# Sheet2.net
KiCad netlist of a schematic drawn in Altium Designer
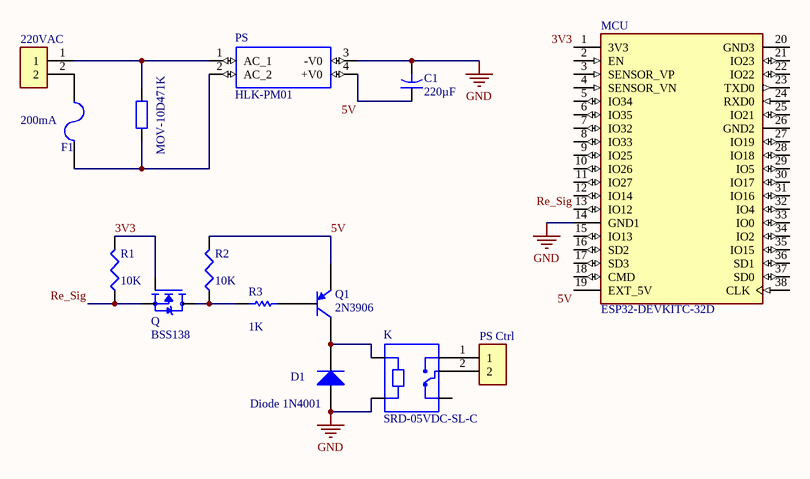
[diagram p0: Sheet2.SchDoc]

(export (version "E")
  (design (tool "Eeschema 10.0.6"))
  (components
    (comp (ref "220VAC")
      (value "282837-2")
      (footprint "TE_282837-2")
      (description "Connector Terminal Blocks Receptacle 2 Position 5.08mm Solder Straight Thru-Hole 13.5A/Contact")
      (fields (field (name "MF") "TE Connectivity") (field (name "DIGI-KEY_PART_NUMBER") "A113320-ND"))
      (libsource (lib "") (part "282837-2_1"))
    )
    (comp (ref "C1")
      (value "220µF")
      (footprint "CAPR5-4X5")
      (description "Capacitor")
      (fields (field (name "Comment") "Cap2") (field (name "PUBLISHER") "Altium Limited"))
      (libsource (lib "Miscellaneous Devices") (part "Cap2"))
    )
    (comp (ref "D1")
      (value "Diode 1N4001")
      (footprint "DO-41")
      (description "1 Amp General Purpose Rectifier")
      (fields (field (name "PUBLISHER") "Altium Limited"))
      (libsource (lib "Miscellaneous Devices") (part "Diode 1N4001"))
    )
    (comp (ref "F1")
      (value "200mA")
      (footprint "PIN-W2/E2.8")
      (description "Fuse")
      (fields (field (name "PUBLISHER") "Altium Limited"))
      (libsource (lib "Miscellaneous Devices") (part "Fuse 2"))
    )
    (comp (ref "K")
      (value "SRD-05VDC-SL-C")
      (footprint "RELAY_SRD-05VDC-SL-C")
      (description "5V Trigger Relay")
      (fields (field (name "MF") "Songle Relay"))
      (libsource (lib "SRD-05VDC-SL-C") (part "SRD-05VDC-SL-C"))
    )
    (comp (ref "MCU")
      (value "ESP32-DEVKITC-32D")
      (footprint "MODULE_ESP32-DEVKITC-32D")
      (fields (field (name "MF") "Espressif Systems"))
      (libsource (lib "ESP32-DEVKITC-32D") (part "ESP32-DEVKITC-32D"))
    )
    (comp (ref "PS")
      (value "HLK-PM01")
      (footprint "HLKPM01")
      (fields (field (name "MF") "Hi-link") (field (name "MP") "hlk-pm01"))
      (libsource (lib "HLK-PM01") (part "HLK-PM01"))
    )
    (comp (ref "PS Ctrl")
      (value "282837-2")
      (footprint "TE_282837-2")
      (description "Connector Terminal Blocks Receptacle 2 Position 5.08mm Solder Straight Thru-Hole 13.5A/Contact")
      (fields (field (name "MF") "TE Connectivity") (field (name "DIGI-KEY_PART_NUMBER") "A113320-ND"))
      (libsource (lib "282837-2") (part "282837-2"))
    )
    (comp (ref "Q")
      (value "BSS138")
      (footprint "SOT95P240X111-3N")
      (description "N-Channel 50V 220mA (Ta) 360mW (Ta) Surface Mount SOT-23-3")
      (fields (field (name "MF") "MICROSS/On Semiconductor"))
      (libsource (lib "BSS138") (part "BSS138"))
    )
    (comp (ref "Q1")
      (value "2N3906")
      (footprint "TO-92A")
      (description "PNP General Purpose Amplifier")
      (fields (field (name "PUBLISHER") "Altium Limited"))
      (libsource (lib "Miscellaneous Devices") (part "2N3906"))
    )
    (comp (ref "R1")
      (value "10K")
      (footprint "J1-0603")
      (description "Resistor")
      (fields (field (name "Comment") "Res3") (field (name "PUBLISHER") "Altium Limited"))
      (libsource (lib "Miscellaneous Devices") (part "Res3"))
    )
    (comp (ref "R2")
      (value "10K")
      (footprint "J1-0603")
      (description "Resistor")
      (fields (field (name "Comment") "Res3") (field (name "PUBLISHER") "Altium Limited"))
      (libsource (lib "Miscellaneous Devices") (part "Res3"))
    )
    (comp (ref "R3")
      (value "1K")
      (footprint "AXIAL-0.3")
      (description "Resistor")
      (fields (field (name "PUBLISHER") "Altium Limited"))
      (libsource (lib "Miscellaneous Devices") (part "Res1"))
    )
    (comp (ref "VAR1")
      (value "MOV-10D471K")
      (footprint "AXIAL-0.4")
      (fields (field (name "PUBLISHER") "Altium Limited"))
      (libsource (lib "Miscellaneous Devices") (part "Res2"))
    )
  )
  (nets
    (net (code "1") (name "/3V3") (class "Default")
      (node (ref "MCU") (pin "1") (pinfunction "3V3_1") (pintype "power_in"))
      (node (ref "Q") (pin "1") (pinfunction "G_1") (pintype "passive"))
      (node (ref "R1") (pin "2") (pinfunction "2_2") (pintype "passive"))
    )
    (net (code "2") (name "/5V") (class "Default")
      (node (ref "C1") (pin "1") (pinfunction "1_1") (pintype "passive"))
      (node (ref "MCU") (pin "19") (pinfunction "EXT_5V_19") (pintype "power_in"))
      (node (ref "PS") (pin "4") (pinfunction "+V0_4") (pintype "bidirectional"))
      (node (ref "Q1") (pin "1") (pinfunction "E_1") (pintype "passive"))
      (node (ref "R2") (pin "2") (pinfunction "2_2") (pintype "passive"))
    )
    (net (code "3") (name "/Re_Sig") (class "Default")
      (node (ref "MCU") (pin "13") (pinfunction "IO12_13") (pintype "bidirectional"))
      (node (ref "Q") (pin "2") (pinfunction "S_2") (pintype "passive"))
      (node (ref "R1") (pin "1") (pinfunction "1_1") (pintype "passive"))
    )
    (net (code "4") (name "GND") (class "Default")
      (node (ref "C1") (pin "2") (pinfunction "2_2") (pintype "passive"))
      (node (ref "D1") (pin "1") (pinfunction "A_1") (pintype "passive"))
      (node (ref "K") (pin "A2") (pinfunction "A2_A2") (pintype "passive"))
      (node (ref "MCU") (pin "14") (pinfunction "GND1_14") (pintype "power_in"))
      (node (ref "PS") (pin "3") (pinfunction "-V0_3") (pintype "bidirectional"))
    )
    (net (code "5") (name "Net-(220VAC-Pad2)") (class "Default")
      (node (ref "220VAC") (pin "2") (pinfunction "2_2") (pintype "passive"))
      (node (ref "F1") (pin "2") (pinfunction "2_2") (pintype "passive"))
    )
    (net (code "6") (name "Net-(D1-K)") (class "Default")
      (node (ref "D1") (pin "2") (pinfunction "K_2") (pintype "passive"))
      (node (ref "K") (pin "A1") (pinfunction "A1_A1") (pintype "passive"))
      (node (ref "Q1") (pin "3") (pinfunction "C_3") (pintype "passive"))
    )
    (net (code "7") (name "Net-(K-PadCOM)") (class "Default")
      (node (ref "K") (pin "COM") (pinfunction "COM_COM") (pintype "passive"))
      (node (ref "PS Ctrl") (pin "2") (pinfunction "2_2") (pintype "passive"))
    )
    (net (code "8") (name "Net-(K-PadNO)") (class "Default")
      (node (ref "K") (pin "NO") (pinfunction "NO_NO") (pintype "passive"))
      (node (ref "PS Ctrl") (pin "1") (pinfunction "1_1") (pintype "passive"))
    )
    (net (code "9") (name "Net-(PS-AC_1)") (class "Default")
      (node (ref "220VAC") (pin "1") (pinfunction "1_1") (pintype "passive"))
      (node (ref "PS") (pin "1") (pinfunction "AC_1_1") (pintype "bidirectional"))
      (node (ref "VAR1") (pin "2") (pinfunction "2_2") (pintype "passive"))
    )
    (net (code "10") (name "Net-(PS-AC_2)") (class "Default")
      (node (ref "F1") (pin "1") (pinfunction "1_1") (pintype "passive"))
      (node (ref "PS") (pin "2") (pinfunction "AC_2_2") (pintype "bidirectional"))
      (node (ref "VAR1") (pin "1") (pinfunction "1_1") (pintype "passive"))
    )
    (net (code "11") (name "Net-(Q-D)") (class "Default")
      (node (ref "Q") (pin "3") (pinfunction "D_3") (pintype "passive"))
      (node (ref "R2") (pin "1") (pinfunction "1_1") (pintype "passive"))
      (node (ref "R3") (pin "1") (pinfunction "1_1") (pintype "passive"))
    )
    (net (code "12") (name "Net-(Q1-B)") (class "Default")
      (node (ref "Q1") (pin "2") (pinfunction "B_2") (pintype "passive"))
      (node (ref "R3") (pin "2") (pinfunction "2_2") (pintype "passive"))
    )
    (net (code "13") (name "unconnected-(K-PadNC)") (class "Default")
      (node (ref "K") (pin "NC") (pinfunction "NC_NC") (pintype "passive"))
    )
    (net (code "14") (name "unconnected-(MCU-CLK-Pad38)") (class "Default")
      (node (ref "MCU") (pin "38") (pinfunction "CLK_38") (pintype "input"))
    )
    (net (code "15") (name "unconnected-(MCU-CMD-Pad18)") (class "Default")
      (node (ref "MCU") (pin "18") (pinfunction "CMD_18") (pintype "bidirectional"))
    )
    (net (code "16") (name "unconnected-(MCU-EN-Pad2)") (class "Default")
      (node (ref "MCU") (pin "2") (pinfunction "EN_2") (pintype "input"))
    )
    (net (code "17") (name "unconnected-(MCU-GND2-Pad26)") (class "Default")
      (node (ref "MCU") (pin "26") (pinfunction "GND2_26") (pintype "power_in"))
    )
    (net (code "18") (name "unconnected-(MCU-GND3-Pad20)") (class "Default")
      (node (ref "MCU") (pin "20") (pinfunction "GND3_20") (pintype "power_in"))
    )
    (net (code "19") (name "unconnected-(MCU-IO0-Pad33)") (class "Default")
      (node (ref "MCU") (pin "33") (pinfunction "IO0_33") (pintype "bidirectional"))
    )
    (net (code "20") (name "unconnected-(MCU-IO2-Pad34)") (class "Default")
      (node (ref "MCU") (pin "34") (pinfunction "IO2_34") (pintype "bidirectional"))
    )
    (net (code "21") (name "unconnected-(MCU-IO4-Pad32)") (class "Default")
      (node (ref "MCU") (pin "32") (pinfunction "IO4_32") (pintype "bidirectional"))
    )
    (net (code "22") (name "unconnected-(MCU-IO5-Pad29)") (class "Default")
      (node (ref "MCU") (pin "29") (pinfunction "IO5_29") (pintype "bidirectional"))
    )
    (net (code "23") (name "unconnected-(MCU-IO13-Pad15)") (class "Default")
      (node (ref "MCU") (pin "15") (pinfunction "IO13_15") (pintype "bidirectional"))
    )
    (net (code "24") (name "unconnected-(MCU-IO14-Pad12)") (class "Default")
      (node (ref "MCU") (pin "12") (pinfunction "IO14_12") (pintype "bidirectional"))
    )
    (net (code "25") (name "unconnected-(MCU-IO15-Pad35)") (class "Default")
      (node (ref "MCU") (pin "35") (pinfunction "IO15_35") (pintype "bidirectional"))
    )
    (net (code "26") (name "unconnected-(MCU-IO16-Pad31)") (class "Default")
      (node (ref "MCU") (pin "31") (pinfunction "IO16_31") (pintype "bidirectional"))
    )
    (net (code "27") (name "unconnected-(MCU-IO17-Pad30)") (class "Default")
      (node (ref "MCU") (pin "30") (pinfunction "IO17_30") (pintype "bidirectional"))
    )
    (net (code "28") (name "unconnected-(MCU-IO18-Pad28)") (class "Default")
      (node (ref "MCU") (pin "28") (pinfunction "IO18_28") (pintype "bidirectional"))
    )
    (net (code "29") (name "unconnected-(MCU-IO19-Pad27)") (class "Default")
      (node (ref "MCU") (pin "27") (pinfunction "IO19_27") (pintype "bidirectional"))
    )
    (net (code "30") (name "unconnected-(MCU-IO21-Pad25)") (class "Default")
      (node (ref "MCU") (pin "25") (pinfunction "IO21_25") (pintype "bidirectional"))
    )
    (net (code "31") (name "unconnected-(MCU-IO22-Pad22)") (class "Default")
      (node (ref "MCU") (pin "22") (pinfunction "IO22_22") (pintype "bidirectional"))
    )
    (net (code "32") (name "unconnected-(MCU-IO23-Pad21)") (class "Default")
      (node (ref "MCU") (pin "21") (pinfunction "IO23_21") (pintype "bidirectional"))
    )
    (net (code "33") (name "unconnected-(MCU-IO25-Pad9)") (class "Default")
      (node (ref "MCU") (pin "9") (pinfunction "IO25_9") (pintype "bidirectional"))
    )
    (net (code "34") (name "unconnected-(MCU-IO26-Pad10)") (class "Default")
      (node (ref "MCU") (pin "10") (pinfunction "IO26_10") (pintype "bidirectional"))
    )
    (net (code "35") (name "unconnected-(MCU-IO27-Pad11)") (class "Default")
      (node (ref "MCU") (pin "11") (pinfunction "IO27_11") (pintype "bidirectional"))
    )
    (net (code "36") (name "unconnected-(MCU-IO32-Pad7)") (class "Default")
      (node (ref "MCU") (pin "7") (pinfunction "IO32_7") (pintype "bidirectional"))
    )
    (net (code "37") (name "unconnected-(MCU-IO33-Pad8)") (class "Default")
      (node (ref "MCU") (pin "8") (pinfunction "IO33_8") (pintype "bidirectional"))
    )
    (net (code "38") (name "unconnected-(MCU-IO34-Pad5)") (class "Default")
      (node (ref "MCU") (pin "5") (pinfunction "IO34_5") (pintype "bidirectional"))
    )
    (net (code "39") (name "unconnected-(MCU-IO35-Pad6)") (class "Default")
      (node (ref "MCU") (pin "6") (pinfunction "IO35_6") (pintype "bidirectional"))
    )
    (net (code "40") (name "unconnected-(MCU-RXD0-Pad24)") (class "Default")
      (node (ref "MCU") (pin "24") (pinfunction "RXD0_24") (pintype "input"))
    )
    (net (code "41") (name "unconnected-(MCU-SD0-Pad37)") (class "Default")
      (node (ref "MCU") (pin "37") (pinfunction "SD0_37") (pintype "bidirectional"))
    )
    (net (code "42") (name "unconnected-(MCU-SD1-Pad36)") (class "Default")
      (node (ref "MCU") (pin "36") (pinfunction "SD1_36") (pintype "bidirectional"))
    )
    (net (code "43") (name "unconnected-(MCU-SD2-Pad16)") (class "Default")
      (node (ref "MCU") (pin "16") (pinfunction "SD2_16") (pintype "bidirectional"))
    )
    (net (code "44") (name "unconnected-(MCU-SD3-Pad17)") (class "Default")
      (node (ref "MCU") (pin "17") (pinfunction "SD3_17") (pintype "bidirectional"))
    )
    (net (code "45") (name "unconnected-(MCU-SENSOR_VN-Pad4)") (class "Default")
      (node (ref "MCU") (pin "4") (pinfunction "SENSOR_VN_4") (pintype "input"))
    )
    (net (code "46") (name "unconnected-(MCU-SENSOR_VP-Pad3)") (class "Default")
      (node (ref "MCU") (pin "3") (pinfunction "SENSOR_VP_3") (pintype "input"))
    )
    (net (code "47") (name "unconnected-(MCU-TXD0-Pad23)") (class "Default")
      (node (ref "MCU") (pin "23") (pinfunction "TXD0_23") (pintype "output"))
    )
  )
)
